# Kuga.net
KiCad netlist of a schematic drawn in EAGLE
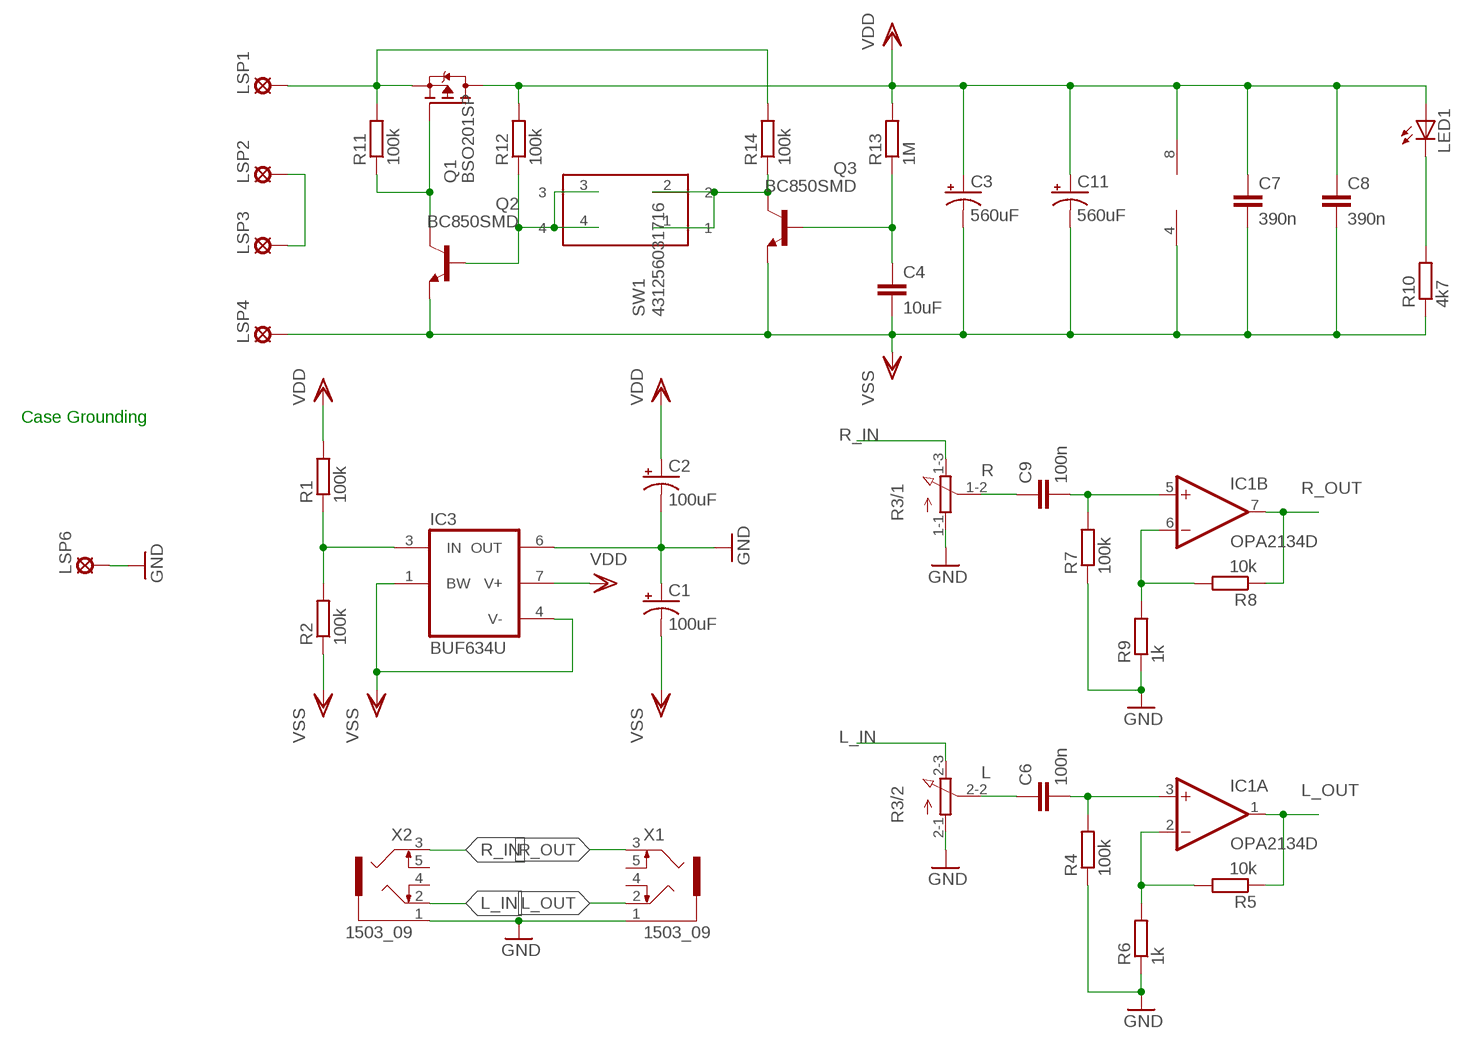
[diagram p0: schematic, sheet 1]

(export (version "E")
  (design (tool "Eeschema 10.0.6"))
  (components
    (comp (ref "C1")
      (value "100uF")
      (footprint "eagle-import:PANASONIC_D")
      (libsource (lib "eagle-import") (part "100UF-POLAR-25V-20%(ELEC)"))
    )
    (comp (ref "C2")
      (value "100uF")
      (footprint "eagle-import:PANASONIC_D")
      (libsource (lib "eagle-import") (part "100UF-POLAR-25V-20%(ELEC)"))
    )
    (comp (ref "C3")
      (value "560uF")
      (footprint "eagle-import:PANASONIC_G")
      (libsource (lib "eagle-import") (part "560UF-PANASONIC_G-25V-20%"))
    )
    (comp (ref "C4")
      (value "10uF")
      (footprint "eagle-import:1210")
      (libsource (lib "eagle-import") (part "10UF-1210-50V-20%"))
    )
    (comp (ref "C6")
      (value "100n")
      (footprint "eagle-import:C1206")
      (libsource (lib "eagle-import") (part "C-EUC1206"))
    )
    (comp (ref "C7")
      (value "390n")
      (footprint "eagle-import:C1206")
      (libsource (lib "eagle-import") (part "C-EUC1206"))
    )
    (comp (ref "C8")
      (value "390n")
      (footprint "eagle-import:C1206")
      (libsource (lib "eagle-import") (part "C-EUC1206"))
    )
    (comp (ref "C9")
      (value "100n")
      (footprint "eagle-import:C1206")
      (libsource (lib "eagle-import") (part "C-EUC1206"))
    )
    (comp (ref "C11")
      (value "560uF")
      (footprint "eagle-import:PANASONIC_G")
      (libsource (lib "eagle-import") (part "560UF-PANASONIC_G-25V-20%"))
    )
    (comp (ref "IC1")
      (value "OPA2134D")
      (footprint "eagle-import:SOIC8")
      (libsource (lib "eagle-import") (part "OPA2134D"))
    )
    (comp (ref "IC3")
      (value "BUF634U")
      (footprint "eagle-import:SO08")
      (fields (field (name "MF") "TEXAS INSTRUMENTS"))
      (libsource (lib "eagle-import") (part "BUF634U"))
    )
    (comp (ref "LED1")
      (value "LED3MM")
      (footprint "eagle-import:LED3MM")
      (libsource (lib "eagle-import") (part "LED3MM"))
    )
    (comp (ref "LSP1")
      (value "LSP10")
      (footprint "eagle-import:LSP10")
      (libsource (lib "eagle-import") (part "LSP10"))
    )
    (comp (ref "LSP2")
      (value "LSP10")
      (footprint "eagle-import:LSP10")
      (libsource (lib "eagle-import") (part "LSP10"))
    )
    (comp (ref "LSP3")
      (value "LSP10")
      (footprint "eagle-import:LSP10")
      (libsource (lib "eagle-import") (part "LSP10"))
    )
    (comp (ref "LSP4")
      (value "LSP10")
      (footprint "eagle-import:LSP10")
      (libsource (lib "eagle-import") (part "LSP10"))
    )
    (comp (ref "LSP6")
      (value "LSP10")
      (footprint "eagle-import:LSP10")
      (libsource (lib "eagle-import") (part "LSP10"))
    )
    (comp (ref "Q1")
      (value "BSO201SP")
      (footprint "eagle-import:SO-8")
      (libsource (lib "eagle-import") (part "BSO201SP"))
    )
    (comp (ref "Q2")
      (value "BC850SMD")
      (footprint "eagle-import:SOT23-BEC")
      (libsource (lib "eagle-import") (part "BC850SMD"))
    )
    (comp (ref "Q3")
      (value "BC850SMD")
      (footprint "eagle-import:SOT23-BEC")
      (libsource (lib "eagle-import") (part "BC850SMD"))
    )
    (comp (ref "R1")
      (value "100k")
      (footprint "eagle-import:R1206")
      (libsource (lib "eagle-import") (part "R-EU_R1206"))
    )
    (comp (ref "R2")
      (value "100k")
      (footprint "eagle-import:R1206")
      (libsource (lib "eagle-import") (part "R-EU_R1206"))
    )
    (comp (ref "R3")
      (value "3RP/1610G")
      (footprint "eagle-import:3RP_1610G")
      (libsource (lib "eagle-import") (part "3RP/1610G"))
    )
    (comp (ref "R4")
      (value "100k")
      (footprint "eagle-import:R1206")
      (libsource (lib "eagle-import") (part "R-EU_R1206"))
    )
    (comp (ref "R5")
      (value "10k")
      (footprint "eagle-import:R1206")
      (libsource (lib "eagle-import") (part "R-EU_R1206"))
    )
    (comp (ref "R6")
      (value "1k")
      (footprint "eagle-import:R1206")
      (libsource (lib "eagle-import") (part "R-EU_R1206"))
    )
    (comp (ref "R7")
      (value "100k")
      (footprint "eagle-import:R1206")
      (libsource (lib "eagle-import") (part "R-EU_R1206"))
    )
    (comp (ref "R8")
      (value "10k")
      (footprint "eagle-import:R1206")
      (libsource (lib "eagle-import") (part "R-EU_R1206"))
    )
    (comp (ref "R9")
      (value "1k")
      (footprint "eagle-import:R1206")
      (libsource (lib "eagle-import") (part "R-EU_R1206"))
    )
    (comp (ref "R10")
      (value "4k7")
      (footprint "eagle-import:R1206")
      (libsource (lib "eagle-import") (part "R-EU_R1206"))
    )
    (comp (ref "R11")
      (value "100k")
      (footprint "eagle-import:R1206")
      (libsource (lib "eagle-import") (part "R-EU_R1206"))
    )
    (comp (ref "R12")
      (value "100k")
      (footprint "eagle-import:R1206")
      (libsource (lib "eagle-import") (part "R-EU_R1206"))
    )
    (comp (ref "R13")
      (value "1M")
      (footprint "eagle-import:R1206")
      (libsource (lib "eagle-import") (part "R-EU_R1206"))
    )
    (comp (ref "R14")
      (value "100k")
      (footprint "eagle-import:R1206")
      (libsource (lib "eagle-import") (part "R-EU_R1206"))
    )
    (comp (ref "SW1")
      (value "431256031716")
      (footprint "eagle-import:431256031716")
      (libsource (lib "eagle-import") (part "431256031716"))
    )
    (comp (ref "X1")
      (value "1503_09")
      (footprint "eagle-import:1503_09")
      (libsource (lib "eagle-import") (part "1503_09"))
    )
    (comp (ref "X2")
      (value "1503_09")
      (footprint "eagle-import:1503_09")
      (libsource (lib "eagle-import") (part "1503_09"))
    )
  )
  (nets
    (net (code "1") (name "/L") (class "Default")
      (node (ref "C6") (pin "1") (pinfunction "1_1") (pintype "passive"))
      (node (ref "R3") (pin "2-2") (pinfunction "S_2-2") (pintype "passive"))
    )
    (net (code "2") (name "/R") (class "Default")
      (node (ref "C9") (pin "1") (pinfunction "1_1") (pintype "passive"))
      (node (ref "R3") (pin "1-2") (pinfunction "S_1-2") (pintype "passive"))
    )
    (net (code "3") (name "GND") (class "Default")
      (node (ref "C1") (pin "+") (pinfunction "+_+") (pintype "passive"))
      (node (ref "C2") (pin "-") (pinfunction "-_-") (pintype "passive"))
      (node (ref "IC3") (pin "6") (pinfunction "OUT_6") (pintype "output"))
      (node (ref "LSP6") (pin "MP") (pinfunction "MP_MP") (pintype "passive"))
      (node (ref "R3") (pin "1-1") (pinfunction "A_1-1") (pintype "passive"))
      (node (ref "R3") (pin "2-1") (pinfunction "A_2-1") (pintype "passive"))
      (node (ref "R4") (pin "1") (pinfunction "1_1") (pintype "passive"))
      (node (ref "R6") (pin "1") (pinfunction "1_1") (pintype "passive"))
      (node (ref "R7") (pin "1") (pinfunction "1_1") (pintype "passive"))
      (node (ref "R9") (pin "1") (pinfunction "1_1") (pintype "passive"))
      (node (ref "X1") (pin "1") (pinfunction "1_1") (pintype "passive"))
      (node (ref "X2") (pin "1") (pinfunction "1_1") (pintype "passive"))
    )
    (net (code "4") (name "L_IN") (class "Default")
      (node (ref "R3") (pin "2-3") (pinfunction "E_2-3") (pintype "passive"))
      (node (ref "X2") (pin "2") (pinfunction "2_2") (pintype "passive"))
    )
    (net (code "5") (name "L_OUT") (class "Default")
      (node (ref "IC1") (pin "1") (pinfunction "OUT_1") (pintype "output"))
      (node (ref "R5") (pin "1") (pinfunction "1_1") (pintype "passive"))
      (node (ref "X1") (pin "2") (pinfunction "2_2") (pintype "passive"))
    )
    (net (code "6") (name "Net-(C4-Pad1)") (class "Default")
      (node (ref "C4") (pin "1") (pinfunction "1_1") (pintype "passive"))
      (node (ref "Q3") (pin "B") (pinfunction "B_B") (pintype "passive"))
      (node (ref "R13") (pin "1") (pinfunction "1_1") (pintype "passive"))
    )
    (net (code "7") (name "Net-(IC1A-+IN)") (class "Default")
      (node (ref "C6") (pin "2") (pinfunction "2_2") (pintype "passive"))
      (node (ref "IC1") (pin "3") (pinfunction "+IN_3") (pintype "input"))
      (node (ref "R4") (pin "2") (pinfunction "2_2") (pintype "passive"))
    )
    (net (code "8") (name "Net-(IC1A--IN)") (class "Default")
      (node (ref "IC1") (pin "2") (pinfunction "-IN_2") (pintype "input"))
      (node (ref "R5") (pin "2") (pinfunction "2_2") (pintype "passive"))
      (node (ref "R6") (pin "2") (pinfunction "2_2") (pintype "passive"))
    )
    (net (code "9") (name "Net-(IC1B-+IN)") (class "Default")
      (node (ref "C9") (pin "2") (pinfunction "2_2") (pintype "passive"))
      (node (ref "IC1") (pin "5") (pinfunction "+IN_5") (pintype "input"))
      (node (ref "R7") (pin "2") (pinfunction "2_2") (pintype "passive"))
    )
    (net (code "10") (name "Net-(IC1B--IN)") (class "Default")
      (node (ref "IC1") (pin "6") (pinfunction "-IN_6") (pintype "input"))
      (node (ref "R8") (pin "2") (pinfunction "2_2") (pintype "passive"))
      (node (ref "R9") (pin "2") (pinfunction "2_2") (pintype "passive"))
    )
    (net (code "11") (name "Net-(IC3-IN)") (class "Default")
      (node (ref "IC3") (pin "3") (pinfunction "IN_3") (pintype "input"))
      (node (ref "R1") (pin "1") (pinfunction "1_1") (pintype "passive"))
      (node (ref "R2") (pin "2") (pinfunction "2_2") (pintype "passive"))
    )
    (net (code "12") (name "Net-(LED1-C)") (class "Default")
      (node (ref "LED1") (pin "K") (pinfunction "C_K") (pintype "passive"))
      (node (ref "R10") (pin "2") (pinfunction "2_2") (pintype "passive"))
    )
    (net (code "13") (name "Net-(LSP1-PadMP)") (class "Default")
      (node (ref "LSP1") (pin "MP") (pinfunction "MP_MP") (pintype "passive"))
      (node (ref "Q1") (pin "1") (pinfunction "S_1") (pintype "passive"))
      (node (ref "Q1") (pin "2") (pinfunction "S_2") (pintype "passive"))
      (node (ref "Q1") (pin "3") (pinfunction "S_3") (pintype "passive"))
      (node (ref "R11") (pin "2") (pinfunction "2_2") (pintype "passive"))
      (node (ref "R14") (pin "2") (pinfunction "2_2") (pintype "passive"))
    )
    (net (code "14") (name "Net-(LSP2-PadMP)") (class "Default")
      (node (ref "LSP2") (pin "MP") (pinfunction "MP_MP") (pintype "passive"))
      (node (ref "LSP3") (pin "MP") (pinfunction "MP_MP") (pintype "passive"))
    )
    (net (code "15") (name "Net-(Q1-G)") (class "Default")
      (node (ref "Q1") (pin "4") (pinfunction "G_4") (pintype "passive"))
      (node (ref "Q2") (pin "C") (pinfunction "C_C") (pintype "passive"))
      (node (ref "R11") (pin "1") (pinfunction "1_1") (pintype "passive"))
    )
    (net (code "16") (name "Net-(Q2-PadB)") (class "Default")
      (node (ref "Q2") (pin "B") (pinfunction "B_B") (pintype "passive"))
      (node (ref "R12") (pin "1") (pinfunction "1_1") (pintype "passive"))
      (node (ref "SW1") (pin "3") (pinfunction "3_3") (pintype "bidirectional"))
      (node (ref "SW1") (pin "4") (pinfunction "4_4") (pintype "bidirectional"))
    )
    (net (code "17") (name "Net-(Q3-PadC)") (class "Default")
      (node (ref "Q3") (pin "C") (pinfunction "C_C") (pintype "passive"))
      (node (ref "R14") (pin "1") (pinfunction "1_1") (pintype "passive"))
      (node (ref "SW1") (pin "1") (pinfunction "1_1") (pintype "bidirectional"))
      (node (ref "SW1") (pin "2") (pinfunction "2_2") (pintype "bidirectional"))
    )
    (net (code "18") (name "R_IN") (class "Default")
      (node (ref "R3") (pin "1-3") (pinfunction "E_1-3") (pintype "passive"))
      (node (ref "X2") (pin "3") (pinfunction "3_3") (pintype "passive"))
    )
    (net (code "19") (name "R_OUT") (class "Default")
      (node (ref "IC1") (pin "7") (pinfunction "OUT_7") (pintype "output"))
      (node (ref "R8") (pin "1") (pinfunction "1_1") (pintype "passive"))
      (node (ref "X1") (pin "3") (pinfunction "3_3") (pintype "passive"))
    )
    (net (code "20") (name "VDD") (class "Default")
      (node (ref "C11") (pin "+") (pinfunction "+_+") (pintype "passive"))
      (node (ref "C2") (pin "+") (pinfunction "+_+") (pintype "passive"))
      (node (ref "C3") (pin "+") (pinfunction "+_+") (pintype "passive"))
      (node (ref "C7") (pin "1") (pinfunction "1_1") (pintype "passive"))
      (node (ref "C8") (pin "1") (pinfunction "1_1") (pintype "passive"))
      (node (ref "IC1") (pin "8") (pinfunction "V+_8") (pintype "power_in"))
      (node (ref "IC3") (pin "7") (pinfunction "V+_7") (pintype "power_in"))
      (node (ref "LED1") (pin "A") (pinfunction "A_A") (pintype "passive"))
      (node (ref "Q1") (pin "5") (pinfunction "D_5") (pintype "passive"))
      (node (ref "Q1") (pin "6") (pinfunction "D_6") (pintype "passive"))
      (node (ref "Q1") (pin "7") (pinfunction "D_7") (pintype "passive"))
      (node (ref "Q1") (pin "8") (pinfunction "D_8") (pintype "passive"))
      (node (ref "R1") (pin "2") (pinfunction "2_2") (pintype "passive"))
      (node (ref "R12") (pin "2") (pinfunction "2_2") (pintype "passive"))
      (node (ref "R13") (pin "2") (pinfunction "2_2") (pintype "passive"))
    )
    (net (code "21") (name "VSS") (class "Default")
      (node (ref "C1") (pin "-") (pinfunction "-_-") (pintype "passive"))
      (node (ref "C11") (pin "-") (pinfunction "-_-") (pintype "passive"))
      (node (ref "C3") (pin "-") (pinfunction "-_-") (pintype "passive"))
      (node (ref "C4") (pin "2") (pinfunction "2_2") (pintype "passive"))
      (node (ref "C7") (pin "2") (pinfunction "2_2") (pintype "passive"))
      (node (ref "C8") (pin "2") (pinfunction "2_2") (pintype "passive"))
      (node (ref "IC1") (pin "4") (pinfunction "V-_4") (pintype "power_in"))
      (node (ref "IC3") (pin "1") (pinfunction "BW_1") (pintype "passive"))
      (node (ref "IC3") (pin "4") (pinfunction "V-_4") (pintype "power_in"))
      (node (ref "LSP4") (pin "MP") (pinfunction "MP_MP") (pintype "passive"))
      (node (ref "Q2") (pin "E") (pinfunction "E_E") (pintype "passive"))
      (node (ref "Q3") (pin "E") (pinfunction "E_E") (pintype "passive"))
      (node (ref "R10") (pin "1") (pinfunction "1_1") (pintype "passive"))
      (node (ref "R2") (pin "1") (pinfunction "1_1") (pintype "passive"))
    )
    (net (code "22") (name "unconnected-(X1-Pad4)") (class "Default")
      (node (ref "X1") (pin "4") (pinfunction "4_4") (pintype "passive"))
    )
    (net (code "23") (name "unconnected-(X1-Pad5)") (class "Default")
      (node (ref "X1") (pin "5") (pinfunction "5_5") (pintype "passive"))
    )
    (net (code "24") (name "unconnected-(X2-Pad4)") (class "Default")
      (node (ref "X2") (pin "4") (pinfunction "4_4") (pintype "passive"))
    )
    (net (code "25") (name "unconnected-(X2-Pad5)") (class "Default")
      (node (ref "X2") (pin "5") (pinfunction "5_5") (pintype "passive"))
    )
  )
)
